# DAC.net
KiCad netlist of a schematic drawn in Altium Designer
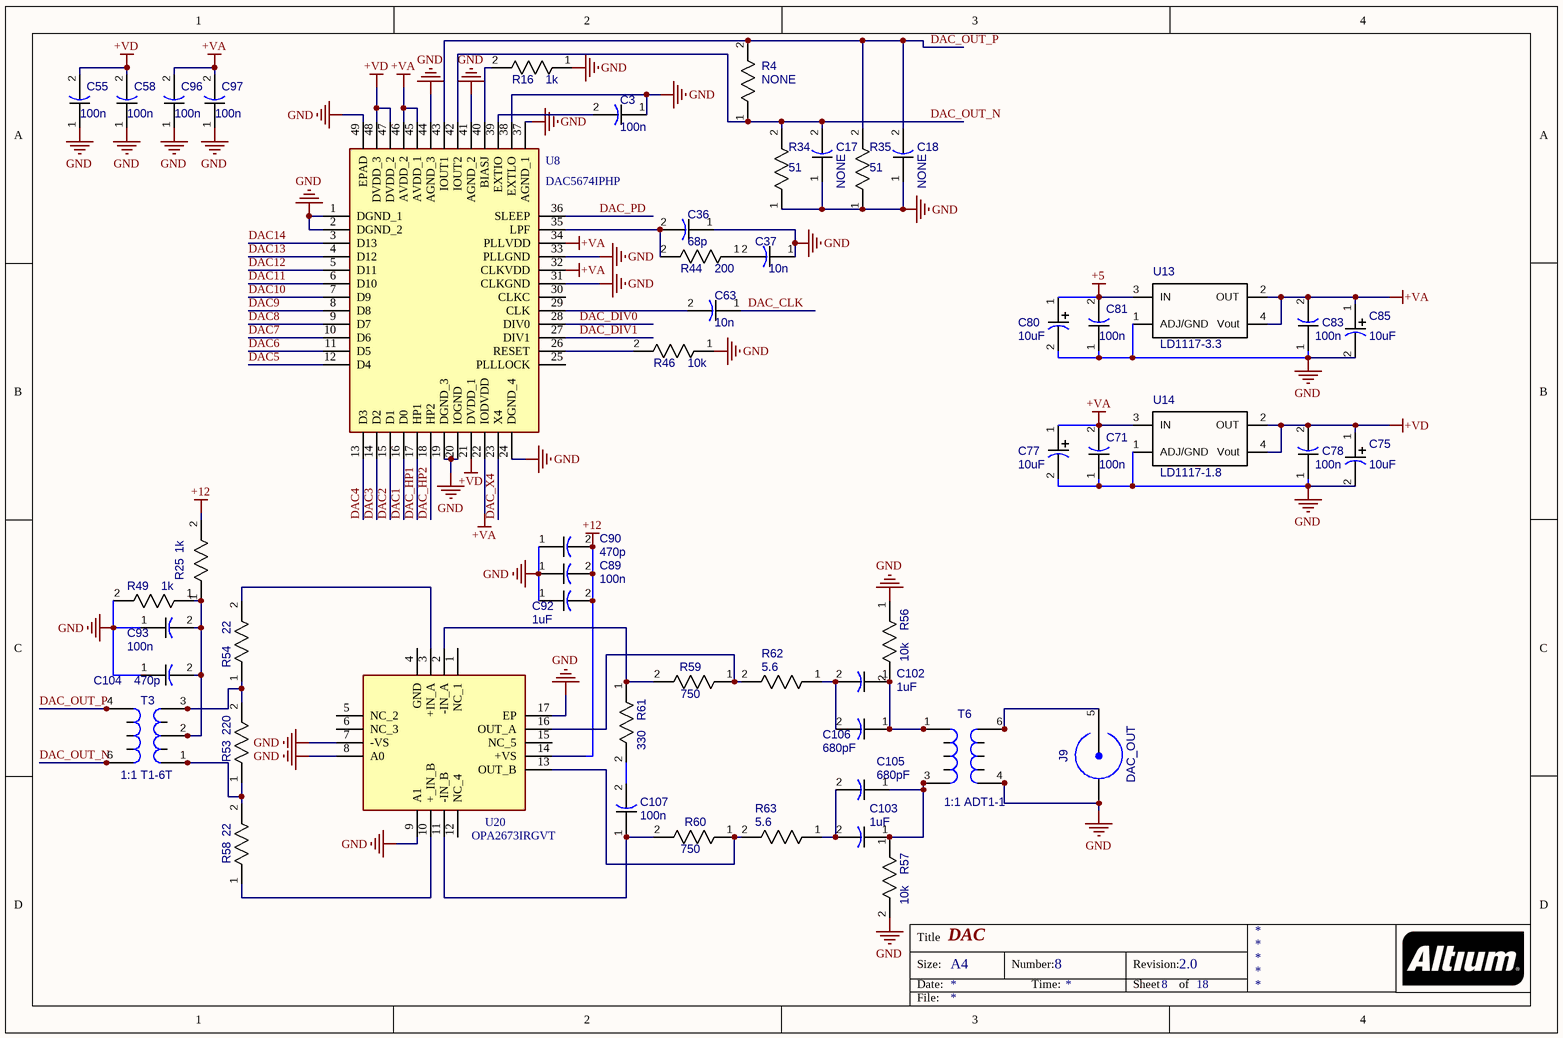
[diagram p0: DAC.SchDoc]

(export (version "E")
  (design (tool "Eeschema 10.0.6"))
  (components
    (comp (ref "C3")
      (value "100n")
      (footprint "CAP_0805")
      (description "CAP_0805")
      (libsource (lib "*") (part "CAP_0805"))
    )
    (comp (ref "C17")
      (value "NONE")
      (footprint "CAP_0805")
      (description "CAP_0805")
      (libsource (lib "*") (part "CAP_0805"))
    )
    (comp (ref "C18")
      (value "NONE")
      (footprint "CAP_0805")
      (description "CAP_0805")
      (libsource (lib "*") (part "CAP_0805"))
    )
    (comp (ref "C36")
      (value "68p")
      (footprint "CAP_0805")
      (description "CAP_0805")
      (libsource (lib "*") (part "CAP_0805"))
    )
    (comp (ref "C37")
      (value "10n")
      (footprint "CAP_0805")
      (description "CAP_0805")
      (libsource (lib "*") (part "CAP_0805"))
    )
    (comp (ref "C55")
      (value "100n")
      (footprint "CAP_0805")
      (description "CAP_0805")
      (libsource (lib "*") (part "CAP_0805"))
    )
    (comp (ref "C58")
      (value "100n")
      (footprint "CAP_0805")
      (description "CAP_0805")
      (libsource (lib "*") (part "CAP_0805"))
    )
    (comp (ref "C63")
      (value "10n")
      (footprint "CAP_0805")
      (description "CAP_0805")
      (libsource (lib "*") (part "CAP_0805"))
    )
    (comp (ref "C71")
      (value "100n")
      (footprint "CAP_0805")
      (description "CAP_0805")
      (libsource (lib "*") (part "CAP_0805"))
    )
    (comp (ref "C75")
      (value "10uF")
      (footprint "EEEFC_sizeB")
      (description "EEEFC_sizeB")
      (libsource (lib "*") (part "EEEFC_sizeB"))
    )
    (comp (ref "C77")
      (value "10uF")
      (footprint "EEEFC_sizeB")
      (description "EEEFC_sizeB")
      (libsource (lib "*") (part "EEEFC_sizeB"))
    )
    (comp (ref "C78")
      (value "100n")
      (footprint "CAP_0805")
      (description "CAP_0805")
      (libsource (lib "*") (part "CAP_0805"))
    )
    (comp (ref "C80")
      (value "10uF")
      (footprint "EEEFC_sizeB")
      (description "EEEFC_sizeB")
      (libsource (lib "*") (part "EEEFC_sizeB"))
    )
    (comp (ref "C81")
      (value "100n")
      (footprint "CAP_0805")
      (description "CAP_0805")
      (libsource (lib "*") (part "CAP_0805"))
    )
    (comp (ref "C83")
      (value "100n")
      (footprint "CAP_0805")
      (description "CAP_0805")
      (libsource (lib "*") (part "CAP_0805"))
    )
    (comp (ref "C85")
      (value "10uF")
      (footprint "EEEFC_sizeB")
      (description "EEEFC_sizeB")
      (libsource (lib "*") (part "EEEFC_sizeB"))
    )
    (comp (ref "C89")
      (value "100n")
      (footprint "CAP_0805")
      (description "CAP_0805")
      (libsource (lib "*") (part "CAP_0805"))
    )
    (comp (ref "C90")
      (value "470p")
      (footprint "CAP_0805")
      (description "CAP_0805")
      (libsource (lib "*") (part "CAP_0805"))
    )
    (comp (ref "C92")
      (value "1uF")
      (footprint "CAP_0805")
      (description "CAP_0805")
      (libsource (lib "*") (part "CAP_0805"))
    )
    (comp (ref "C93")
      (value "100n")
      (footprint "CAP_0805")
      (description "CAP_0805")
      (libsource (lib "*") (part "CAP_0805"))
    )
    (comp (ref "C96")
      (value "100n")
      (footprint "CAP_0805")
      (description "CAP_0805")
      (libsource (lib "*") (part "CAP_0805"))
    )
    (comp (ref "C97")
      (value "100n")
      (footprint "CAP_0805")
      (description "CAP_0805")
      (libsource (lib "*") (part "CAP_0805"))
    )
    (comp (ref "C102")
      (value "1uF")
      (footprint "CAP_1206")
      (description "CAP_1206")
      (libsource (lib "*") (part "CAP_1206"))
    )
    (comp (ref "C103")
      (value "1uF")
      (footprint "CAP_1206")
      (description "CAP_1206")
      (libsource (lib "*") (part "CAP_1206"))
    )
    (comp (ref "C104")
      (value "470p")
      (footprint "CAP_0805")
      (description "CAP_0805")
      (libsource (lib "*") (part "CAP_0805"))
    )
    (comp (ref "C105")
      (value "680pF")
      (footprint "CAP_1206")
      (description "CAP_1206")
      (libsource (lib "*") (part "CAP_1206"))
    )
    (comp (ref "C106")
      (value "680pF")
      (footprint "CAP_1206")
      (description "CAP_1206")
      (libsource (lib "*") (part "CAP_1206"))
    )
    (comp (ref "C107")
      (value "100n")
      (footprint "CAP_0805")
      (description "CAP_0805")
      (libsource (lib "*") (part "CAP_0805"))
    )
    (comp (ref "J9")
      (value "DAC_OUT")
      (footprint "31-5431")
      (description "SMA")
      (libsource (lib "RF-UNIT_1") (part "31-5431"))
    )
    (comp (ref "R4")
      (value "NONE")
      (footprint "RES_0805")
      (description "RES_0805")
      (libsource (lib "*") (part "RES_0805"))
    )
    (comp (ref "R16")
      (value "1k")
      (footprint "RES_0805")
      (description "RES_0805")
      (libsource (lib "*") (part "RES_0805"))
    )
    (comp (ref "R25")
      (value "1k")
      (footprint "RES_0805")
      (description "RES_0805")
      (libsource (lib "*") (part "RES_0805"))
    )
    (comp (ref "R34")
      (value "51")
      (footprint "RES_0805")
      (description "RES_0805")
      (libsource (lib "*") (part "RES_0805"))
    )
    (comp (ref "R35")
      (value "51")
      (footprint "RES_0805")
      (description "RES_0805")
      (libsource (lib "*") (part "RES_0805"))
    )
    (comp (ref "R44")
      (value "200")
      (footprint "RES_0805")
      (description "RES_0805")
      (libsource (lib "*") (part "RES_0805"))
    )
    (comp (ref "R46")
      (value "10k")
      (footprint "RES_0805")
      (description "RES_0805")
      (libsource (lib "*") (part "RES_0805"))
    )
    (comp (ref "R49")
      (value "1k")
      (footprint "RES_0805")
      (description "RES_0805")
      (libsource (lib "*") (part "RES_0805"))
    )
    (comp (ref "R53")
      (value "220")
      (footprint "RES_0805")
      (description "RES_0805")
      (libsource (lib "*") (part "RES_0805"))
    )
    (comp (ref "R54")
      (value "22")
      (footprint "RES_0805")
      (description "RES_0805")
      (libsource (lib "*") (part "RES_0805"))
    )
    (comp (ref "R56")
      (value "10k")
      (footprint "RES_0805")
      (description "RES_0805")
      (libsource (lib "*") (part "RES_0805"))
    )
    (comp (ref "R57")
      (value "10k")
      (footprint "RES_0805")
      (description "RES_0805")
      (libsource (lib "*") (part "RES_0805"))
    )
    (comp (ref "R58")
      (value "22")
      (footprint "RES_0805")
      (description "RES_0805")
      (libsource (lib "*") (part "RES_0805"))
    )
    (comp (ref "R59")
      (value "750")
      (footprint "RES_0805")
      (description "RES_0805")
      (libsource (lib "*") (part "RES_0805"))
    )
    (comp (ref "R60")
      (value "750")
      (footprint "RES_0805")
      (description "RES_0805")
      (libsource (lib "*") (part "RES_0805"))
    )
    (comp (ref "R61")
      (value "330")
      (footprint "RES_0805")
      (description "RES_0805")
      (libsource (lib "*") (part "RES_0805"))
    )
    (comp (ref "R62")
      (value "5.6")
      (footprint "RES_1206")
      (description "RES_1206")
      (libsource (lib "*") (part "RES_1206"))
    )
    (comp (ref "R63")
      (value "5.6")
      (footprint "RES_1206")
      (description "RES_1206")
      (libsource (lib "*") (part "RES_1206"))
    )
    (comp (ref "T3")
      (value "1:1 T1-6T")
      (footprint "TRANSF_ACORE2")
      (description "Transformer")
      (libsource (lib "MOTHERBOARD_1") (part "TRANSF_ACORE2"))
    )
    (comp (ref "T6")
      (value "1:1 ADT1-1")
      (footprint "TRANSF_ACORE")
      (description "Transformer")
      (libsource (lib "MOTHERBOARD_1") (part "TRANSF_ACORE"))
    )
    (comp (ref "U8")
      (value "DAC5674IPHP")
      (footprint "SamacSys:QFP50P900X900X100-49N")
      (description "Integrated Circuit")
      (libsource (lib "*") (part "DAC5674IPHP"))
    )
    (comp (ref "U13")
      (value "LD1117-3.3")
      (footprint "LT1117CST-3.3")
      (description "LT1117CST-3.3")
      (libsource (lib "*") (part "LT1117CST-3.3"))
    )
    (comp (ref "U14")
      (value "LD1117-1.8")
      (footprint "LT1117CST-3.3")
      (description "LT1117CST-1.8")
      (libsource (lib "*") (part "LT1117CST-3.3"))
    )
    (comp (ref "U20")
      (value "OPA2673IRGVT")
      (footprint "SamacSys:QFN65P400X400X100-17N-D")
      (description "Integrated Circuit")
      (fields
        (field (name "MOUSER PART NUMBER") "595-OPA2673IRGVT")
        (field (name "RS PART NUMBER") "8122587P")
      )
      (libsource (lib "*") (part "OPA2673IRGVT"))
    )
  )
  (nets
    (net (code "1") (name "+5") (class "Default")
      (node (ref "C80") (pin "1") (pinfunction "PLUS_1") (pintype "passive"))
      (node (ref "C81") (pin "2") (pinfunction "2_2") (pintype "passive"))
      (node (ref "U13") (pin "3") (pinfunction "IN_3") (pintype "passive"))
    )
    (net (code "2") (name "+12") (class "Default")
      (node (ref "C89") (pin "2") (pinfunction "2_2") (pintype "passive"))
      (node (ref "C90") (pin "2") (pinfunction "2_2") (pintype "passive"))
      (node (ref "C92") (pin "2") (pinfunction "2_2") (pintype "passive"))
      (node (ref "R25") (pin "2") (pinfunction "2_2") (pintype "passive"))
      (node (ref "U20") (pin "14") (pinfunction "+VS_14") (pintype "passive"))
    )
    (net (code "3") (name "+VA") (class "Default")
      (node (ref "C71") (pin "2") (pinfunction "2_2") (pintype "passive"))
      (node (ref "C77") (pin "1") (pinfunction "PLUS_1") (pintype "passive"))
      (node (ref "C83") (pin "2") (pinfunction "2_2") (pintype "passive"))
      (node (ref "C85") (pin "1") (pinfunction "PLUS_1") (pintype "passive"))
      (node (ref "C96") (pin "2") (pinfunction "2_2") (pintype "passive"))
      (node (ref "C97") (pin "2") (pinfunction "2_2") (pintype "passive"))
      (node (ref "U13") (pin "2") (pinfunction "OUT_2") (pintype "passive"))
      (node (ref "U13") (pin "4") (pinfunction "Vout_4") (pintype "passive"))
      (node (ref "U14") (pin "3") (pinfunction "IN_3") (pintype "passive"))
      (node (ref "U8") (pin "22") (pinfunction "IODVDD_22") (pintype "passive"))
      (node (ref "U8") (pin "32") (pinfunction "CLKVDD_32") (pintype "passive"))
      (node (ref "U8") (pin "34") (pinfunction "PLLVDD_34") (pintype "passive"))
      (node (ref "U8") (pin "45") (pinfunction "AVDD_1_45") (pintype "passive"))
      (node (ref "U8") (pin "46") (pinfunction "AVDD_2_46") (pintype "passive"))
    )
    (net (code "4") (name "+VD") (class "Default")
      (node (ref "C55") (pin "2") (pinfunction "2_2") (pintype "passive"))
      (node (ref "C58") (pin "2") (pinfunction "2_2") (pintype "passive"))
      (node (ref "C75") (pin "1") (pinfunction "PLUS_1") (pintype "passive"))
      (node (ref "C78") (pin "2") (pinfunction "2_2") (pintype "passive"))
      (node (ref "U14") (pin "2") (pinfunction "OUT_2") (pintype "passive"))
      (node (ref "U14") (pin "4") (pinfunction "Vout_4") (pintype "passive"))
      (node (ref "U8") (pin "21") (pinfunction "DVDD_1_21") (pintype "passive"))
      (node (ref "U8") (pin "47") (pinfunction "DVDD_2_47") (pintype "passive"))
      (node (ref "U8") (pin "48") (pinfunction "DVDD_3_48") (pintype "passive"))
    )
    (net (code "5") (name "/DAC1") (class "Default")
      (node (ref "U8") (pin "16") (pinfunction "D0_16") (pintype "passive"))
    )
    (net (code "6") (name "/DAC2") (class "Default")
      (node (ref "U8") (pin "15") (pinfunction "D1_15") (pintype "passive"))
    )
    (net (code "7") (name "/DAC3") (class "Default")
      (node (ref "U8") (pin "14") (pinfunction "D2_14") (pintype "passive"))
    )
    (net (code "8") (name "/DAC4") (class "Default")
      (node (ref "U8") (pin "13") (pinfunction "D3_13") (pintype "passive"))
    )
    (net (code "9") (name "/DAC5") (class "Default")
      (node (ref "U8") (pin "12") (pinfunction "D4_12") (pintype "passive"))
    )
    (net (code "10") (name "/DAC6") (class "Default")
      (node (ref "U8") (pin "11") (pinfunction "D5_11") (pintype "passive"))
    )
    (net (code "11") (name "/DAC7") (class "Default")
      (node (ref "U8") (pin "10") (pinfunction "D6_10") (pintype "passive"))
    )
    (net (code "12") (name "/DAC8") (class "Default")
      (node (ref "U8") (pin "9") (pinfunction "D7_9") (pintype "passive"))
    )
    (net (code "13") (name "/DAC9") (class "Default")
      (node (ref "U8") (pin "8") (pinfunction "D8_8") (pintype "passive"))
    )
    (net (code "14") (name "/DAC10") (class "Default")
      (node (ref "U8") (pin "7") (pinfunction "D9_7") (pintype "passive"))
    )
    (net (code "15") (name "/DAC11") (class "Default")
      (node (ref "U8") (pin "6") (pinfunction "D10_6") (pintype "passive"))
    )
    (net (code "16") (name "/DAC12") (class "Default")
      (node (ref "U8") (pin "5") (pinfunction "D11_5") (pintype "passive"))
    )
    (net (code "17") (name "/DAC13") (class "Default")
      (node (ref "U8") (pin "4") (pinfunction "D12_4") (pintype "passive"))
    )
    (net (code "18") (name "/DAC14") (class "Default")
      (node (ref "U8") (pin "3") (pinfunction "D13_3") (pintype "passive"))
    )
    (net (code "19") (name "/DAC_CLK") (class "Default")
      (node (ref "C63") (pin "1") (pinfunction "1_1") (pintype "passive"))
    )
    (net (code "20") (name "/DAC_DIV0") (class "Default")
      (node (ref "U8") (pin "28") (pinfunction "DIV0_28") (pintype "passive"))
    )
    (net (code "21") (name "/DAC_DIV1") (class "Default")
      (node (ref "U8") (pin "27") (pinfunction "DIV1_27") (pintype "passive"))
    )
    (net (code "22") (name "/DAC_HP1") (class "Default")
      (node (ref "U8") (pin "17") (pinfunction "HP1_17") (pintype "passive"))
    )
    (net (code "23") (name "/DAC_HP2") (class "Default")
      (node (ref "U8") (pin "18") (pinfunction "HP2_18") (pintype "passive"))
    )
    (net (code "24") (name "/DAC_OUT_N") (class "Default")
      (node (ref "C17") (pin "2") (pinfunction "2_2") (pintype "passive"))
      (node (ref "R34") (pin "2") (pinfunction "2_2") (pintype "passive"))
      (node (ref "R4") (pin "1") (pinfunction "1_1") (pintype "passive"))
      (node (ref "T3") (pin "10") (pinfunction "0_10") (pintype "passive"))
      (node (ref "T3") (pin "6") (pinfunction "P2_6") (pintype "passive"))
      (node (ref "U8") (pin "42") (pinfunction "IOUT2_42") (pintype "passive"))
    )
    (net (code "25") (name "/DAC_OUT_P") (class "Default")
      (node (ref "C18") (pin "2") (pinfunction "2_2") (pintype "passive"))
      (node (ref "R35") (pin "2") (pinfunction "2_2") (pintype "passive"))
      (node (ref "R4") (pin "2") (pinfunction "2_2") (pintype "passive"))
      (node (ref "T3") (pin "11") (pinfunction "0_11") (pintype "passive"))
      (node (ref "T3") (pin "4") (pinfunction "P1_4") (pintype "passive"))
      (node (ref "U8") (pin "43") (pinfunction "IOUT1_43") (pintype "passive"))
    )
    (net (code "26") (name "/DAC_PD") (class "Default")
      (node (ref "U8") (pin "36") (pinfunction "SLEEP_36") (pintype "passive"))
    )
    (net (code "27") (name "/DAC_X4") (class "Default")
      (node (ref "U8") (pin "23") (pinfunction "X4_23") (pintype "passive"))
    )
    (net (code "28") (name "GND") (class "Default")
      (node (ref "C104") (pin "1") (pinfunction "1_1") (pintype "passive"))
      (node (ref "C17") (pin "1") (pinfunction "1_1") (pintype "passive"))
      (node (ref "C18") (pin "1") (pinfunction "1_1") (pintype "passive"))
      (node (ref "C3") (pin "1") (pinfunction "1_1") (pintype "passive"))
      (node (ref "C36") (pin "1") (pinfunction "1_1") (pintype "passive"))
      (node (ref "C37") (pin "1") (pinfunction "1_1") (pintype "passive"))
      (node (ref "C55") (pin "1") (pinfunction "1_1") (pintype "passive"))
      (node (ref "C58") (pin "1") (pinfunction "1_1") (pintype "passive"))
      (node (ref "C71") (pin "1") (pinfunction "1_1") (pintype "passive"))
      (node (ref "C75") (pin "2") (pinfunction "MINUS_2") (pintype "passive"))
      (node (ref "C77") (pin "2") (pinfunction "MINUS_2") (pintype "passive"))
      (node (ref "C78") (pin "1") (pinfunction "1_1") (pintype "passive"))
      (node (ref "C80") (pin "2") (pinfunction "MINUS_2") (pintype "passive"))
      (node (ref "C81") (pin "1") (pinfunction "1_1") (pintype "passive"))
      (node (ref "C83") (pin "1") (pinfunction "1_1") (pintype "passive"))
      (node (ref "C85") (pin "2") (pinfunction "MINUS_2") (pintype "passive"))
      (node (ref "C89") (pin "1") (pinfunction "1_1") (pintype "passive"))
      (node (ref "C90") (pin "1") (pinfunction "1_1") (pintype "passive"))
      (node (ref "C92") (pin "1") (pinfunction "1_1") (pintype "passive"))
      (node (ref "C93") (pin "1") (pinfunction "1_1") (pintype "passive"))
      (node (ref "C96") (pin "1") (pinfunction "1_1") (pintype "passive"))
      (node (ref "C97") (pin "1") (pinfunction "1_1") (pintype "passive"))
      (node (ref "J9") (pin "1") (pinfunction "GND_1") (pintype "passive"))
      (node (ref "J9") (pin "2") (pinfunction "GND_2") (pintype "passive"))
      (node (ref "J9") (pin "3") (pinfunction "GND_3") (pintype "passive"))
      (node (ref "J9") (pin "4") (pinfunction "GND_4") (pintype "passive"))
      (node (ref "R16") (pin "1") (pinfunction "1_1") (pintype "passive"))
      (node (ref "R34") (pin "1") (pinfunction "1_1") (pintype "passive"))
      (node (ref "R35") (pin "1") (pinfunction "1_1") (pintype "passive"))
      (node (ref "R46") (pin "1") (pinfunction "1_1") (pintype "passive"))
      (node (ref "R49") (pin "2") (pinfunction "2_2") (pintype "passive"))
      (node (ref "R56") (pin "1") (pinfunction "1_1") (pintype "passive"))
      (node (ref "R57") (pin "2") (pinfunction "2_2") (pintype "passive"))
      (node (ref "T6") (pin "11") (pinfunction "0_11") (pintype "passive"))
      (node (ref "T6") (pin "4") (pinfunction "S2_4") (pintype "passive"))
      (node (ref "U13") (pin "1") (pinfunction "ADJ/GND_1") (pintype "passive"))
      (node (ref "U14") (pin "1") (pinfunction "ADJ/GND_1") (pintype "passive"))
      (node (ref "U20") (pin "17") (pinfunction "EP_17") (pintype "passive"))
      (node (ref "U20") (pin "7") (pinfunction "-VS_7") (pintype "passive"))
      (node (ref "U20") (pin "8") (pinfunction "A0_8") (pintype "passive"))
      (node (ref "U20") (pin "9") (pinfunction "A1_9") (pintype "passive"))
      (node (ref "U8") (pin "1") (pinfunction "DGND_1_1") (pintype "passive"))
      (node (ref "U8") (pin "19") (pinfunction "DGND_3_19") (pintype "passive"))
      (node (ref "U8") (pin "2") (pinfunction "DGND_2_2") (pintype "passive"))
      (node (ref "U8") (pin "20") (pinfunction "IOGND_20") (pintype "passive"))
      (node (ref "U8") (pin "24") (pinfunction "DGND_4_24") (pintype "passive"))
      (node (ref "U8") (pin "31") (pinfunction "CLKGND_31") (pintype "passive"))
      (node (ref "U8") (pin "33") (pinfunction "PLLGND_33") (pintype "passive"))
      (node (ref "U8") (pin "37") (pinfunction "AGND_1_37") (pintype "passive"))
      (node (ref "U8") (pin "38") (pinfunction "EXTLO_38") (pintype "passive"))
      (node (ref "U8") (pin "41") (pinfunction "AGND_2_41") (pintype "passive"))
      (node (ref "U8") (pin "44") (pinfunction "AGND_3_44") (pintype "passive"))
      (node (ref "U8") (pin "49") (pinfunction "EPAD_49") (pintype "passive"))
    )
    (net (code "29") (name "Net-(C37-Pad2)") (class "Default")
      (node (ref "C37") (pin "2") (pinfunction "2_2") (pintype "passive"))
      (node (ref "R44") (pin "1") (pinfunction "1_1") (pintype "passive"))
    )
    (net (code "30") (name "Net-(C102-Pad2)") (class "Default")
      (node (ref "C102") (pin "2") (pinfunction "2_2") (pintype "passive"))
      (node (ref "C106") (pin "2") (pinfunction "2_2") (pintype "passive"))
      (node (ref "R62") (pin "1") (pinfunction "1_1") (pintype "passive"))
    )
    (net (code "31") (name "Net-(C103-Pad2)") (class "Default")
      (node (ref "C103") (pin "2") (pinfunction "2_2") (pintype "passive"))
      (node (ref "C105") (pin "2") (pinfunction "2_2") (pintype "passive"))
      (node (ref "R63") (pin "1") (pinfunction "1_1") (pintype "passive"))
    )
    (net (code "32") (name "Net-(C107-Pad2)") (class "Default")
      (node (ref "C107") (pin "2") (pinfunction "2_2") (pintype "passive"))
      (node (ref "R61") (pin "2") (pinfunction "2_2") (pintype "passive"))
    )
    (net (code "33") (name "Net-(J9-CON)") (class "Default")
      (node (ref "J9") (pin "5") (pinfunction "CON_5") (pintype "passive"))
      (node (ref "T6") (pin "10") (pinfunction "0_10") (pintype "passive"))
      (node (ref "T6") (pin "6") (pinfunction "S1_6") (pintype "passive"))
    )
    (net (code "34") (name "Net-(T3-S1)") (class "Default")
      (node (ref "R53") (pin "2") (pinfunction "2_2") (pintype "passive"))
      (node (ref "R54") (pin "1") (pinfunction "1_1") (pintype "passive"))
      (node (ref "T3") (pin "3") (pinfunction "S1_3") (pintype "passive"))
      (node (ref "T3") (pin "9") (pinfunction "0_9") (pintype "passive"))
    )
    (net (code "35") (name "Net-(T3-S2)") (class "Default")
      (node (ref "C104") (pin "2") (pinfunction "2_2") (pintype "passive"))
      (node (ref "C93") (pin "2") (pinfunction "2_2") (pintype "passive"))
      (node (ref "R25") (pin "1") (pinfunction "1_1") (pintype "passive"))
      (node (ref "R49") (pin "1") (pinfunction "1_1") (pintype "passive"))
      (node (ref "T3") (pin "2") (pinfunction "S2_2") (pintype "passive"))
      (node (ref "T3") (pin "8") (pinfunction "0_8") (pintype "passive"))
    )
    (net (code "36") (name "Net-(T3-S3)") (class "Default")
      (node (ref "R53") (pin "1") (pinfunction "1_1") (pintype "passive"))
      (node (ref "R58") (pin "2") (pinfunction "2_2") (pintype "passive"))
      (node (ref "T3") (pin "1") (pinfunction "S3_1") (pintype "passive"))
      (node (ref "T3") (pin "7") (pinfunction "0_7") (pintype "passive"))
    )
    (net (code "37") (name "Net-(T6-P1)") (class "Default")
      (node (ref "C102") (pin "1") (pinfunction "1_1") (pintype "passive"))
      (node (ref "C106") (pin "1") (pinfunction "1_1") (pintype "passive"))
      (node (ref "R56") (pin "2") (pinfunction "2_2") (pintype "passive"))
      (node (ref "T6") (pin "1") (pinfunction "P1_1") (pintype "passive"))
      (node (ref "T6") (pin "7") (pinfunction "0_7") (pintype "passive"))
    )
    (net (code "38") (name "Net-(T6-P2)") (class "Default")
      (node (ref "C103") (pin "1") (pinfunction "1_1") (pintype "passive"))
      (node (ref "C105") (pin "1") (pinfunction "1_1") (pintype "passive"))
      (node (ref "R57") (pin "1") (pinfunction "1_1") (pintype "passive"))
      (node (ref "T6") (pin "3") (pinfunction "P2_3") (pintype "passive"))
      (node (ref "T6") (pin "9") (pinfunction "0_9") (pintype "passive"))
    )
    (net (code "39") (name "Net-(U8-BIASJ)") (class "Default")
      (node (ref "R16") (pin "2") (pinfunction "2_2") (pintype "passive"))
      (node (ref "U8") (pin "40") (pinfunction "BIASJ_40") (pintype "passive"))
    )
    (net (code "40") (name "Net-(U8-CLK)") (class "Default")
      (node (ref "C63") (pin "2") (pinfunction "2_2") (pintype "passive"))
      (node (ref "U8") (pin "29") (pinfunction "CLK_29") (pintype "passive"))
    )
    (net (code "41") (name "Net-(U8-EXTIO)") (class "Default")
      (node (ref "C3") (pin "2") (pinfunction "2_2") (pintype "passive"))
      (node (ref "U8") (pin "39") (pinfunction "EXTIO_39") (pintype "passive"))
    )
    (net (code "42") (name "Net-(U8-LPF)") (class "Default")
      (node (ref "C36") (pin "2") (pinfunction "2_2") (pintype "passive"))
      (node (ref "R44") (pin "2") (pinfunction "2_2") (pintype "passive"))
      (node (ref "U8") (pin "35") (pinfunction "LPF_35") (pintype "passive"))
    )
    (net (code "43") (name "Net-(U8-RESET)") (class "Default")
      (node (ref "R46") (pin "2") (pinfunction "2_2") (pintype "passive"))
      (node (ref "U8") (pin "26") (pinfunction "RESET_26") (pintype "passive"))
    )
    (net (code "44") (name "Net-(U20-+IN_A)") (class "Default")
      (node (ref "R54") (pin "2") (pinfunction "2_2") (pintype "passive"))
      (node (ref "U20") (pin "3") (pinfunction "+IN_A_3") (pintype "passive"))
    )
    (net (code "45") (name "Net-(U20-+_IN_B)") (class "Default")
      (node (ref "R58") (pin "1") (pinfunction "1_1") (pintype "passive"))
      (node (ref "U20") (pin "10") (pinfunction "+_IN_B_10") (pintype "passive"))
    )
    (net (code "46") (name "Net-(U20--IN_A)") (class "Default")
      (node (ref "R59") (pin "2") (pinfunction "2_2") (pintype "passive"))
      (node (ref "R61") (pin "1") (pinfunction "1_1") (pintype "passive"))
      (node (ref "U20") (pin "2") (pinfunction "-IN_A_2") (pintype "passive"))
    )
    (net (code "47") (name "Net-(U20--IN_B)") (class "Default")
      (node (ref "C107") (pin "1") (pinfunction "1_1") (pintype "passive"))
      (node (ref "R60") (pin "2") (pinfunction "2_2") (pintype "passive"))
      (node (ref "U20") (pin "11") (pinfunction "-IN_B_11") (pintype "passive"))
    )
    (net (code "48") (name "Net-(U20-OUT_A)") (class "Default")
      (node (ref "R59") (pin "1") (pinfunction "1_1") (pintype "passive"))
      (node (ref "R62") (pin "2") (pinfunction "2_2") (pintype "passive"))
      (node (ref "U20") (pin "16") (pinfunction "OUT_A_16") (pintype "passive"))
    )
    (net (code "49") (name "Net-(U20-OUT_B)") (class "Default")
      (node (ref "R60") (pin "1") (pinfunction "1_1") (pintype "passive"))
      (node (ref "R63") (pin "2") (pinfunction "2_2") (pintype "passive"))
      (node (ref "U20") (pin "13") (pinfunction "OUT_B_13") (pintype "passive"))
    )
    (net (code "50") (name "unconnected-(T6-0-Pad8)") (class "Default")
      (node (ref "T6") (pin "8") (pinfunction "0_8") (pintype "passive"))
    )
    (net (code "51") (name "unconnected-(U8-CLKC-Pad30)") (class "Default")
      (node (ref "U8") (pin "30") (pinfunction "CLKC_30") (pintype "passive"))
    )
    (net (code "52") (name "unconnected-(U8-PLLLOCK-Pad25)") (class "Default")
      (node (ref "U8") (pin "25") (pinfunction "PLLLOCK_25") (pintype "passive"))
    )
    (net (code "53") (name "unconnected-(U20-GND-Pad4)") (class "Default")
      (node (ref "U20") (pin "4") (pinfunction "GND_4") (pintype "passive"))
    )
    (net (code "54") (name "unconnected-(U20-NC_1-Pad1)") (class "Default")
      (node (ref "U20") (pin "1") (pinfunction "NC_1_1") (pintype "passive"))
    )
    (net (code "55") (name "unconnected-(U20-NC_2-Pad5)") (class "Default")
      (node (ref "U20") (pin "5") (pinfunction "NC_2_5") (pintype "passive"))
    )
    (net (code "56") (name "unconnected-(U20-NC_3-Pad6)") (class "Default")
      (node (ref "U20") (pin "6") (pinfunction "NC_3_6") (pintype "passive"))
    )
    (net (code "57") (name "unconnected-(U20-NC_4-Pad12)") (class "Default")
      (node (ref "U20") (pin "12") (pinfunction "NC_4_12") (pintype "passive"))
    )
    (net (code "58") (name "unconnected-(U20-NC_5-Pad15)") (class "Default")
      (node (ref "U20") (pin "15") (pinfunction "NC_5_15") (pintype "passive"))
    )
  )
)
